# 10-DPLL-1.net
KiCad netlist of a schematic drawn in Altium Designer
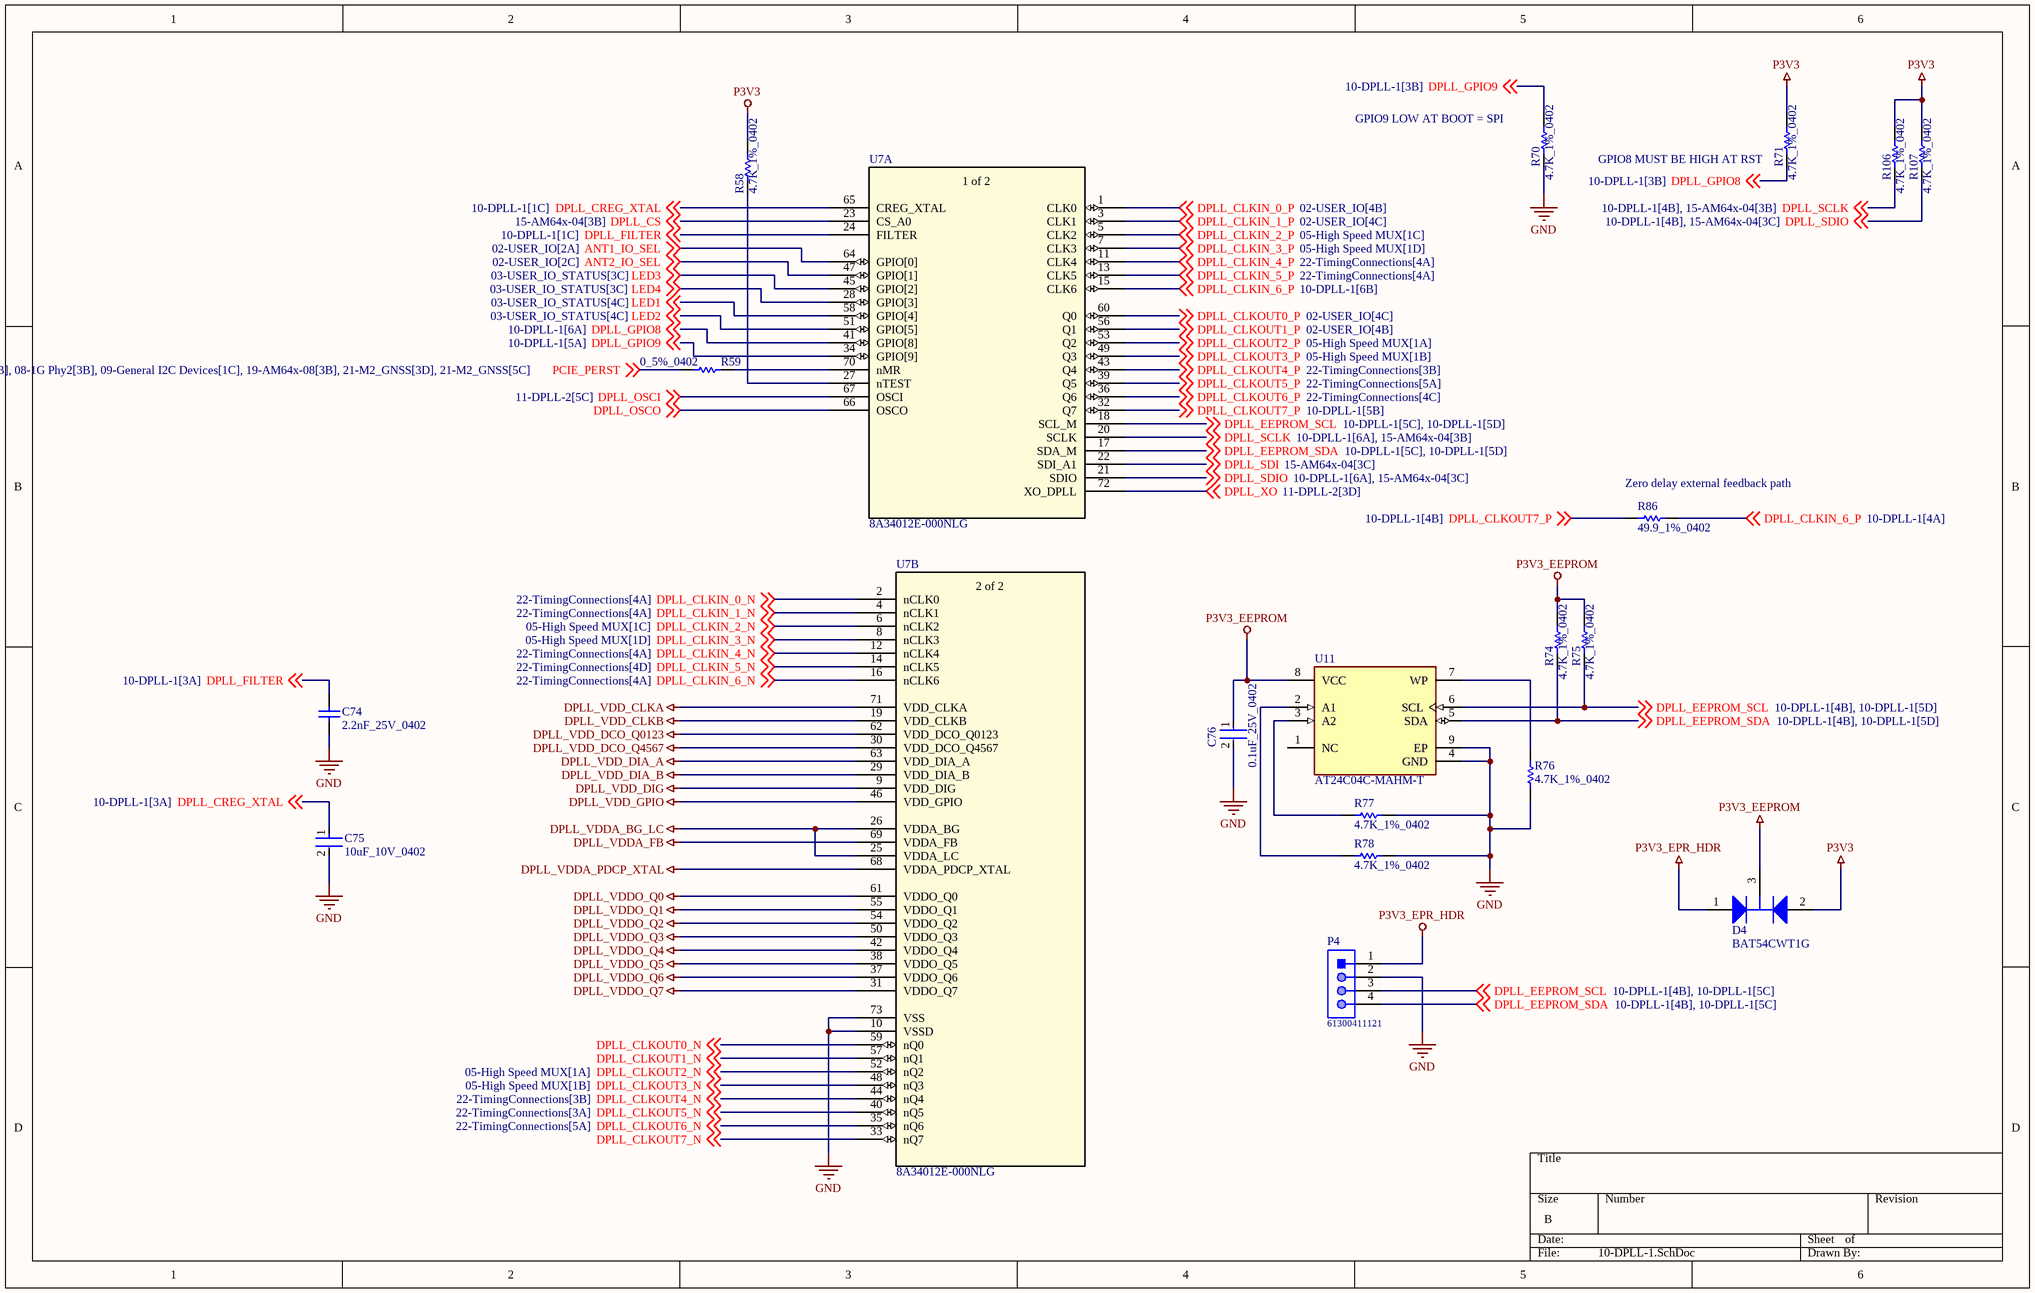
[diagram p0: 10-DPLL-1.SchDoc]

(export (version "E")
  (design (tool "Eeschema 10.0.6"))
  (components
    (comp (ref "C74")
      (value "2.2nF_25V_0402")
      (footprint "CAPC1005X56X25LL10T15")
      (fields
        (field (name "MANUFACTURER") "AVX Interconnect / Elco")
        (field (name "PART NUMBER") "04025C222JAT2A")
      )
      (libsource (lib "Altium Content Vault") (part "CAP"))
    )
    (comp (ref "C75")
      (value "10uF_10V_0402")
      (footprint "FP-CL05A106MP5NUNC-MFG")
      (description "CAP CER 10UF 10V X5R 0402")
      (fields
        (field (name "OCTOPART") "https://octopart.com/cl05a106mp5nunc-samsung-22457395")
        (field (name "TOLERANCE") "20%")
      )
      (libsource (lib "Altium Content Vault") (part "b4654b650e69147ec39a6b967a45e02"))
    )
    (comp (ref "C76")
      (value "0.1uF_25V_0402")
      (footprint "FP-0402-L_1_0_1-W_0_5_0_1-IPC_C")
      (description "General Purpose Ceramic Capacitor, 0402, 100nF, 10%, X7R, 15%, 25V")
      (fields (field (name "VOLTAGE") "25V") (field (name "TOLERANCE") "10%"))
      (libsource (lib "Altium Content Vault") (part "b4654b650e69147ec39a6b967a45e02"))
    )
    (comp (ref "D4")
      (value "BAT54CWT1G")
      (footprint "ONSC-SOT-323-3-419-04_V")
      (description "Dual Series Cathode Schottky Barrier Diodes, 3-Pin SOT-323, Pb-Free, Tape and Reel")
      (fields (field (name "MANUFACTURER") "On Semiconductor"))
      (libsource (lib "Altium Content Vault") (part "ONSC-D-A1A2K3-3"))
    )
    (comp (ref "P4")
      (value "61300411121")
      (footprint "61300411121")
      (description "THT Vertical Pin Header WR-PHD, Pitch 2.54 mm, Single Row, 4 pins")
      (fields (field (name "MANUFACTURER") "Wurth Elektronik") (field (name "PUBLISHER") "WurthElektronik"))
      (libsource (lib "Altium Content Vault") (part "WE-CN-1P-M-R4"))
    )
    (comp (ref "R58")
      (value "4.7K_1%_0402")
      (footprint "RESC1005X40X25NL10T10")
      (fields (field (name "MANUFACTURER") "Bourns") (field (name "PART NUMBER") "CR0402-FX-4701GLF"))
      (libsource (lib "Altium Content Vault") (part "RES"))
    )
    (comp (ref "R59")
      (value "0_5%_0402")
      (footprint "RESC1005X40X25LL10T10")
      (fields (field (name "MANUFACTURER") "KOA Speer") (field (name "PART NUMBER") "RK73Z1ETTP"))
      (libsource (lib "Altium Content Vault") (part "RES"))
    )
    (comp (ref "R70")
      (value "4.7K_1%_0402")
      (footprint "RESC1005X40X25NL10T10")
      (fields (field (name "MANUFACTURER") "Bourns") (field (name "PART NUMBER") "CR0402-FX-4701GLF"))
      (libsource (lib "Altium Content Vault") (part "RES"))
    )
    (comp (ref "R71")
      (value "4.7K_1%_0402")
      (footprint "RESC1005X40X25NL10T10")
      (fields (field (name "MANUFACTURER") "Bourns") (field (name "PART NUMBER") "CR0402-FX-4701GLF"))
      (libsource (lib "Altium Content Vault") (part "RES"))
    )
    (comp (ref "R74")
      (value "4.7K_1%_0402")
      (footprint "RESC1005X40X25NL10T10")
      (fields (field (name "MANUFACTURER") "Bourns") (field (name "PART NUMBER") "CR0402-FX-4701GLF"))
      (libsource (lib "Altium Content Vault") (part "RES"))
    )
    (comp (ref "R75")
      (value "4.7K_1%_0402")
      (footprint "RESC1005X40X25NL10T10")
      (fields (field (name "MANUFACTURER") "Bourns") (field (name "PART NUMBER") "CR0402-FX-4701GLF"))
      (libsource (lib "Altium Content Vault") (part "RES"))
    )
    (comp (ref "R76")
      (value "4.7K_1%_0402")
      (footprint "RESC1005X40X25NL10T10")
      (fields (field (name "MANUFACTURER") "Bourns") (field (name "PART NUMBER") "CR0402-FX-4701GLF"))
      (libsource (lib "Altium Content Vault") (part "RES"))
    )
    (comp (ref "R77")
      (value "4.7K_1%_0402")
      (footprint "RESC1005X40X25NL10T10")
      (fields (field (name "MANUFACTURER") "Bourns") (field (name "PART NUMBER") "CR0402-FX-4701GLF"))
      (libsource (lib "Altium Content Vault") (part "RES"))
    )
    (comp (ref "R78")
      (value "4.7K_1%_0402")
      (footprint "RESC1005X40X25NL10T10")
      (fields (field (name "MANUFACTURER") "Bourns") (field (name "PART NUMBER") "CR0402-FX-4701GLF"))
      (libsource (lib "Altium Content Vault") (part "RES"))
    )
    (comp (ref "R86")
      (value "49.9_1%_0402")
      (footprint "RESC1005X40X25NL10T10")
      (fields (field (name "PART NUMBER") "RK73H1ETTP49R9F") (field (name "MANUFACTURER") "KOA Speer"))
      (libsource (lib "Altium Content Vault") (part "RES"))
    )
    (comp (ref "R106")
      (value "4.7K_1%_0402")
      (footprint "RESC1005X40X25NL10T10")
      (fields (field (name "MANUFACTURER") "Bourns") (field (name "PART NUMBER") "CR0402-FX-4701GLF"))
      (libsource (lib "Altium Content Vault") (part "RES"))
    )
    (comp (ref "R107")
      (value "4.7K_1%_0402")
      (footprint "RESC1005X40X25NL10T10")
      (fields (field (name "MANUFACTURER") "Bourns") (field (name "PART NUMBER") "CR0402-FX-4701GLF"))
      (libsource (lib "Altium Content Vault") (part "RES"))
    )
    (comp (ref "U7")
      (value "8A34012E-000NLG")
      (footprint "QFN_2E-000NLG_REN")
      (description "No Description Available")
      (libsource (lib "8A34002E-000NLG") (part "8A34002E-000NLG"))
    )
    (comp (ref "U11")
      (value "AT24C04C-MAHM-T")
      (footprint "FP-C04-21355-Q4B-IPC_B")
      (description "IC EEPROM 4KBIT I2C 1MHZ 8UDFN")
      (libsource (lib "Altium Content Vault") (part "94da826279c6e6069df6e860fe9c8cd"))
    )
  )
  (nets
    (net (code "1") (name "ANT1_IO_SEL") (class "Default")
      (node (ref "U7") (pin "64") (pinfunction "GPIO[0]_64") (pintype "bidirectional"))
    )
    (net (code "2") (name "ANT2_IO_SEL") (class "Default")
      (node (ref "U7") (pin "47") (pinfunction "GPIO[1]_47") (pintype "bidirectional"))
    )
    (net (code "3") (name "DPLL_CLKIN_0_N") (class "Default")
      (node (ref "U7") (pin "2") (pinfunction "nCLK0_2") (pintype "passive"))
    )
    (net (code "4") (name "DPLL_CLKIN_0_P") (class "Default")
      (node (ref "U7") (pin "1") (pinfunction "CLK0_1") (pintype "bidirectional"))
    )
    (net (code "5") (name "DPLL_CLKIN_1_N") (class "Default")
      (node (ref "U7") (pin "4") (pinfunction "nCLK1_4") (pintype "passive"))
    )
    (net (code "6") (name "DPLL_CLKIN_1_P") (class "Default")
      (node (ref "U7") (pin "3") (pinfunction "CLK1_3") (pintype "bidirectional"))
    )
    (net (code "7") (name "DPLL_CLKIN_2_N") (class "Default")
      (node (ref "U7") (pin "6") (pinfunction "nCLK2_6") (pintype "passive"))
    )
    (net (code "8") (name "DPLL_CLKIN_2_P") (class "Default")
      (node (ref "U7") (pin "5") (pinfunction "CLK2_5") (pintype "bidirectional"))
    )
    (net (code "9") (name "DPLL_CLKIN_3_N") (class "Default")
      (node (ref "U7") (pin "8") (pinfunction "nCLK3_8") (pintype "passive"))
    )
    (net (code "10") (name "DPLL_CLKIN_3_P") (class "Default")
      (node (ref "U7") (pin "7") (pinfunction "CLK3_7") (pintype "bidirectional"))
    )
    (net (code "11") (name "DPLL_CLKIN_4_N") (class "Default")
      (node (ref "U7") (pin "12") (pinfunction "nCLK4_12") (pintype "passive"))
    )
    (net (code "12") (name "DPLL_CLKIN_4_P") (class "Default")
      (node (ref "U7") (pin "11") (pinfunction "CLK4_11") (pintype "bidirectional"))
    )
    (net (code "13") (name "DPLL_CLKIN_5_N") (class "Default")
      (node (ref "U7") (pin "14") (pinfunction "nCLK5_14") (pintype "passive"))
    )
    (net (code "14") (name "DPLL_CLKIN_5_P") (class "Default")
      (node (ref "U7") (pin "13") (pinfunction "CLK5_13") (pintype "bidirectional"))
    )
    (net (code "15") (name "DPLL_CLKIN_6_N") (class "Default")
      (node (ref "U7") (pin "16") (pinfunction "nCLK6_16") (pintype "passive"))
    )
    (net (code "16") (name "DPLL_CLKIN_6_P") (class "Default")
      (node (ref "R86") (pin "2") (pinfunction "2_2") (pintype "passive"))
      (node (ref "U7") (pin "15") (pinfunction "CLK6_15") (pintype "bidirectional"))
    )
    (net (code "17") (name "DPLL_CLKOUT0_N") (class "Default")
      (node (ref "U7") (pin "59") (pinfunction "nQ0_59") (pintype "bidirectional"))
    )
    (net (code "18") (name "DPLL_CLKOUT0_P") (class "Default")
      (node (ref "U7") (pin "60") (pinfunction "Q0_60") (pintype "bidirectional"))
    )
    (net (code "19") (name "DPLL_CLKOUT1_N") (class "Default")
      (node (ref "U7") (pin "57") (pinfunction "nQ1_57") (pintype "bidirectional"))
    )
    (net (code "20") (name "DPLL_CLKOUT1_P") (class "Default")
      (node (ref "U7") (pin "56") (pinfunction "Q1_56") (pintype "bidirectional"))
    )
    (net (code "21") (name "DPLL_CLKOUT2_N") (class "Default")
      (node (ref "U7") (pin "52") (pinfunction "nQ2_52") (pintype "bidirectional"))
    )
    (net (code "22") (name "DPLL_CLKOUT2_P") (class "Default")
      (node (ref "U7") (pin "53") (pinfunction "Q2_53") (pintype "bidirectional"))
    )
    (net (code "23") (name "DPLL_CLKOUT3_N") (class "Default")
      (node (ref "U7") (pin "48") (pinfunction "nQ3_48") (pintype "bidirectional"))
    )
    (net (code "24") (name "DPLL_CLKOUT3_P") (class "Default")
      (node (ref "U7") (pin "49") (pinfunction "Q3_49") (pintype "bidirectional"))
    )
    (net (code "25") (name "DPLL_CLKOUT4_N") (class "Default")
      (node (ref "U7") (pin "44") (pinfunction "nQ4_44") (pintype "bidirectional"))
    )
    (net (code "26") (name "DPLL_CLKOUT4_P") (class "Default")
      (node (ref "U7") (pin "43") (pinfunction "Q4_43") (pintype "bidirectional"))
    )
    (net (code "27") (name "DPLL_CLKOUT5_N") (class "Default")
      (node (ref "U7") (pin "40") (pinfunction "nQ5_40") (pintype "bidirectional"))
    )
    (net (code "28") (name "DPLL_CLKOUT5_P") (class "Default")
      (node (ref "U7") (pin "39") (pinfunction "Q5_39") (pintype "bidirectional"))
    )
    (net (code "29") (name "DPLL_CLKOUT6_N") (class "Default")
      (node (ref "U7") (pin "35") (pinfunction "nQ6_35") (pintype "bidirectional"))
    )
    (net (code "30") (name "DPLL_CLKOUT6_P") (class "Default")
      (node (ref "U7") (pin "36") (pinfunction "Q6_36") (pintype "bidirectional"))
    )
    (net (code "31") (name "DPLL_CLKOUT7_N") (class "Default")
      (node (ref "U7") (pin "33") (pinfunction "nQ7_33") (pintype "bidirectional"))
    )
    (net (code "32") (name "DPLL_CLKOUT7_P") (class "Default")
      (node (ref "R86") (pin "1") (pinfunction "1_1") (pintype "passive"))
      (node (ref "U7") (pin "32") (pinfunction "Q7_32") (pintype "bidirectional"))
    )
    (net (code "33") (name "DPLL_CREG_XTAL") (class "Default")
      (node (ref "C75") (pin "1") (pinfunction "1_1") (pintype "passive"))
      (node (ref "U7") (pin "65") (pinfunction "CREG_XTAL_65") (pintype "passive"))
    )
    (net (code "34") (name "DPLL_CS") (class "Default")
      (node (ref "U7") (pin "23") (pinfunction "CS_A0_23") (pintype "passive"))
    )
    (net (code "35") (name "DPLL_EEPROM_SCL") (class "Default")
      (node (ref "P4") (pin "3") (pinfunction "3_3") (pintype "passive"))
      (node (ref "R75") (pin "2") (pinfunction "2_2") (pintype "passive"))
      (node (ref "U11") (pin "6") (pinfunction "SCL_6") (pintype "input"))
      (node (ref "U7") (pin "18") (pinfunction "SCL_M_18") (pintype "passive"))
    )
    (net (code "36") (name "DPLL_EEPROM_SDA") (class "Default")
      (node (ref "P4") (pin "4") (pinfunction "4_4") (pintype "passive"))
      (node (ref "R74") (pin "2") (pinfunction "2_2") (pintype "passive"))
      (node (ref "U11") (pin "5") (pinfunction "SDA_5") (pintype "bidirectional"))
      (node (ref "U7") (pin "17") (pinfunction "SDA_M_17") (pintype "passive"))
    )
    (net (code "37") (name "DPLL_FILTER") (class "Default")
      (node (ref "C74") (pin "2") (pinfunction "2_2") (pintype "passive"))
      (node (ref "U7") (pin "24") (pinfunction "FILTER_24") (pintype "passive"))
    )
    (net (code "38") (name "DPLL_GPIO8") (class "Default")
      (node (ref "R71") (pin "2") (pinfunction "2_2") (pintype "passive"))
      (node (ref "U7") (pin "41") (pinfunction "GPIO[8]_41") (pintype "bidirectional"))
    )
    (net (code "39") (name "DPLL_GPIO9") (class "Default")
      (node (ref "R70") (pin "1") (pinfunction "1_1") (pintype "passive"))
      (node (ref "U7") (pin "34") (pinfunction "GPIO[9]_34") (pintype "bidirectional"))
    )
    (net (code "40") (name "DPLL_OSCI") (class "Default")
      (node (ref "U7") (pin "67") (pinfunction "OSCI_67") (pintype "passive"))
    )
    (net (code "41") (name "DPLL_OSCO") (class "Default")
      (node (ref "U7") (pin "66") (pinfunction "OSCO_66") (pintype "passive"))
    )
    (net (code "42") (name "DPLL_SCLK") (class "Default")
      (node (ref "R106") (pin "2") (pinfunction "2_2") (pintype "passive"))
      (node (ref "U7") (pin "20") (pinfunction "SCLK_20") (pintype "passive"))
    )
    (net (code "43") (name "DPLL_SDI") (class "Default")
      (node (ref "U7") (pin "22") (pinfunction "SDI_A1_22") (pintype "passive"))
    )
    (net (code "44") (name "DPLL_SDIO") (class "Default")
      (node (ref "R107") (pin "2") (pinfunction "2_2") (pintype "passive"))
      (node (ref "U7") (pin "21") (pinfunction "SDIO_21") (pintype "passive"))
    )
    (net (code "45") (name "DPLL_VDDA_BG_LC") (class "Default")
      (node (ref "U7") (pin "25") (pinfunction "VDDA_LC_25") (pintype "power_in"))
      (node (ref "U7") (pin "26") (pinfunction "VDDA_BG_26") (pintype "power_in"))
    )
    (net (code "46") (name "DPLL_VDDA_FB") (class "Default")
      (node (ref "U7") (pin "69") (pinfunction "VDDA_FB_69") (pintype "power_in"))
    )
    (net (code "47") (name "DPLL_VDDA_PDCP_XTAL") (class "Default")
      (node (ref "U7") (pin "68") (pinfunction "VDDA_PDCP_XTAL_68") (pintype "power_in"))
    )
    (net (code "48") (name "DPLL_VDDO_Q0") (class "Default")
      (node (ref "U7") (pin "61") (pinfunction "VDDO_Q0_61") (pintype "power_in"))
    )
    (net (code "49") (name "DPLL_VDDO_Q1") (class "Default")
      (node (ref "U7") (pin "55") (pinfunction "VDDO_Q1_55") (pintype "power_in"))
    )
    (net (code "50") (name "DPLL_VDDO_Q2") (class "Default")
      (node (ref "U7") (pin "54") (pinfunction "VDDO_Q2_54") (pintype "power_in"))
    )
    (net (code "51") (name "DPLL_VDDO_Q3") (class "Default")
      (node (ref "U7") (pin "50") (pinfunction "VDDO_Q3_50") (pintype "power_in"))
    )
    (net (code "52") (name "DPLL_VDDO_Q4") (class "Default")
      (node (ref "U7") (pin "42") (pinfunction "VDDO_Q4_42") (pintype "power_in"))
    )
    (net (code "53") (name "DPLL_VDDO_Q5") (class "Default")
      (node (ref "U7") (pin "38") (pinfunction "VDDO_Q5_38") (pintype "power_in"))
    )
    (net (code "54") (name "DPLL_VDDO_Q6") (class "Default")
      (node (ref "U7") (pin "37") (pinfunction "VDDO_Q6_37") (pintype "power_in"))
    )
    (net (code "55") (name "DPLL_VDDO_Q7") (class "Default")
      (node (ref "U7") (pin "31") (pinfunction "VDDO_Q7_31") (pintype "power_in"))
    )
    (net (code "56") (name "DPLL_VDD_CLKA") (class "Default")
      (node (ref "U7") (pin "71") (pinfunction "VDD_CLKA_71") (pintype "power_in"))
    )
    (net (code "57") (name "DPLL_VDD_CLKB") (class "Default")
      (node (ref "U7") (pin "19") (pinfunction "VDD_CLKB_19") (pintype "power_in"))
    )
    (net (code "58") (name "DPLL_VDD_DCO_Q0123") (class "Default")
      (node (ref "U7") (pin "62") (pinfunction "VDD_DCO_Q0123_62") (pintype "power_in"))
    )
    (net (code "59") (name "DPLL_VDD_DCO_Q4567") (class "Default")
      (node (ref "U7") (pin "30") (pinfunction "VDD_DCO_Q4567_30") (pintype "power_in"))
    )
    (net (code "60") (name "DPLL_VDD_DIA_A") (class "Default")
      (node (ref "U7") (pin "63") (pinfunction "VDD_DIA_A_63") (pintype "power_in"))
    )
    (net (code "61") (name "DPLL_VDD_DIA_B") (class "Default")
      (node (ref "U7") (pin "29") (pinfunction "VDD_DIA_B_29") (pintype "power_in"))
    )
    (net (code "62") (name "DPLL_VDD_DIG") (class "Default")
      (node (ref "U7") (pin "9") (pinfunction "VDD_DIG_9") (pintype "power_in"))
    )
    (net (code "63") (name "DPLL_VDD_GPIO") (class "Default")
      (node (ref "U7") (pin "46") (pinfunction "VDD_GPIO_46") (pintype "power_in"))
    )
    (net (code "64") (name "DPLL_XO") (class "Default")
      (node (ref "U7") (pin "72") (pinfunction "XO_DPLL_72") (pintype "passive"))
    )
    (net (code "65") (name "GND") (class "Default")
      (node (ref "C74") (pin "1") (pinfunction "1_1") (pintype "passive"))
      (node (ref "C75") (pin "2") (pinfunction "2_2") (pintype "passive"))
      (node (ref "C76") (pin "2") (pinfunction "2_2") (pintype "passive"))
      (node (ref "P4") (pin "2") (pinfunction "2_2") (pintype "passive"))
      (node (ref "R70") (pin "2") (pinfunction "2_2") (pintype "passive"))
      (node (ref "R76") (pin "2") (pinfunction "2_2") (pintype "passive"))
      (node (ref "R77") (pin "1") (pinfunction "1_1") (pintype "passive"))
      (node (ref "R78") (pin "2") (pinfunction "2_2") (pintype "passive"))
      (node (ref "U11") (pin "4") (pinfunction "GND_4") (pintype "power_in"))
      (node (ref "U11") (pin "9") (pinfunction "EP_9") (pintype "power_in"))
      (node (ref "U7") (pin "10") (pinfunction "VSSD_10") (pintype "power_in"))
      (node (ref "U7") (pin "73") (pinfunction "VSS_73") (pintype "power_in"))
    )
    (net (code "66") (name "LED1") (class "Default")
      (node (ref "U7") (pin "58") (pinfunction "GPIO[4]_58") (pintype "bidirectional"))
    )
    (net (code "67") (name "LED2") (class "Default")
      (node (ref "U7") (pin "51") (pinfunction "GPIO[5]_51") (pintype "bidirectional"))
    )
    (net (code "68") (name "LED3") (class "Default")
      (node (ref "U7") (pin "45") (pinfunction "GPIO[2]_45") (pintype "bidirectional"))
    )
    (net (code "69") (name "LED4") (class "Default")
      (node (ref "U7") (pin "28") (pinfunction "GPIO[3]_28") (pintype "bidirectional"))
    )
    (net (code "70") (name "Net-(U7A-nMR)") (class "Default")
      (node (ref "R59") (pin "2") (pinfunction "2_2") (pintype "passive"))
      (node (ref "U7") (pin "70") (pinfunction "nMR_70") (pintype "passive"))
    )
    (net (code "71") (name "Net-(U7A-nTEST)") (class "Default")
      (node (ref "R58") (pin "1") (pinfunction "1_1") (pintype "passive"))
      (node (ref "U7") (pin "27") (pinfunction "nTEST_27") (pintype "passive"))
    )
    (net (code "72") (name "Net-(U11-A1)") (class "Default")
      (node (ref "R78") (pin "1") (pinfunction "1_1") (pintype "passive"))
      (node (ref "U11") (pin "2") (pinfunction "A1_2") (pintype "input"))
    )
    (net (code "73") (name "Net-(U11-A2)") (class "Default")
      (node (ref "R77") (pin "2") (pinfunction "2_2") (pintype "passive"))
      (node (ref "U11") (pin "3") (pinfunction "A2_3") (pintype "input"))
    )
    (net (code "74") (name "Net-(U11-WP)") (class "Default")
      (node (ref "R76") (pin "1") (pinfunction "1_1") (pintype "passive"))
      (node (ref "U11") (pin "7") (pinfunction "WP_7") (pintype "passive"))
    )
    (net (code "75") (name "P3V3") (class "Default")
      (node (ref "D4") (pin "2") (pinfunction "A2_2") (pintype "passive"))
      (node (ref "R106") (pin "1") (pinfunction "1_1") (pintype "passive"))
      (node (ref "R107") (pin "1") (pinfunction "1_1") (pintype "passive"))
      (node (ref "R58") (pin "2") (pinfunction "2_2") (pintype "passive"))
      (node (ref "R71") (pin "1") (pinfunction "1_1") (pintype "passive"))
    )
    (net (code "76") (name "P3V3_EEPROM") (class "Default")
      (node (ref "C76") (pin "1") (pinfunction "1_1") (pintype "passive"))
      (node (ref "D4") (pin "3") (pinfunction "K_3") (pintype "passive"))
      (node (ref "R74") (pin "1") (pinfunction "1_1") (pintype "passive"))
      (node (ref "R75") (pin "1") (pinfunction "1_1") (pintype "passive"))
      (node (ref "U11") (pin "8") (pinfunction "VCC_8") (pintype "power_in"))
    )
    (net (code "77") (name "P3V3_EPR_HDR") (class "Default")
      (node (ref "D4") (pin "1") (pinfunction "A1_1") (pintype "passive"))
      (node (ref "P4") (pin "1") (pinfunction "1_1") (pintype "passive"))
    )
    (net (code "78") (name "PCIE_PERST") (class "Default")
      (node (ref "R59") (pin "1") (pinfunction "1_1") (pintype "passive"))
    )
    (net (code "79") (name "unconnected-(U11-NC-Pad1)") (class "Default")
      (node (ref "U11") (pin "1") (pinfunction "NC_1") (pintype "passive"))
    )
  )
)
